# design.net
KiCad netlist of a schematic drawn in Altium Designer
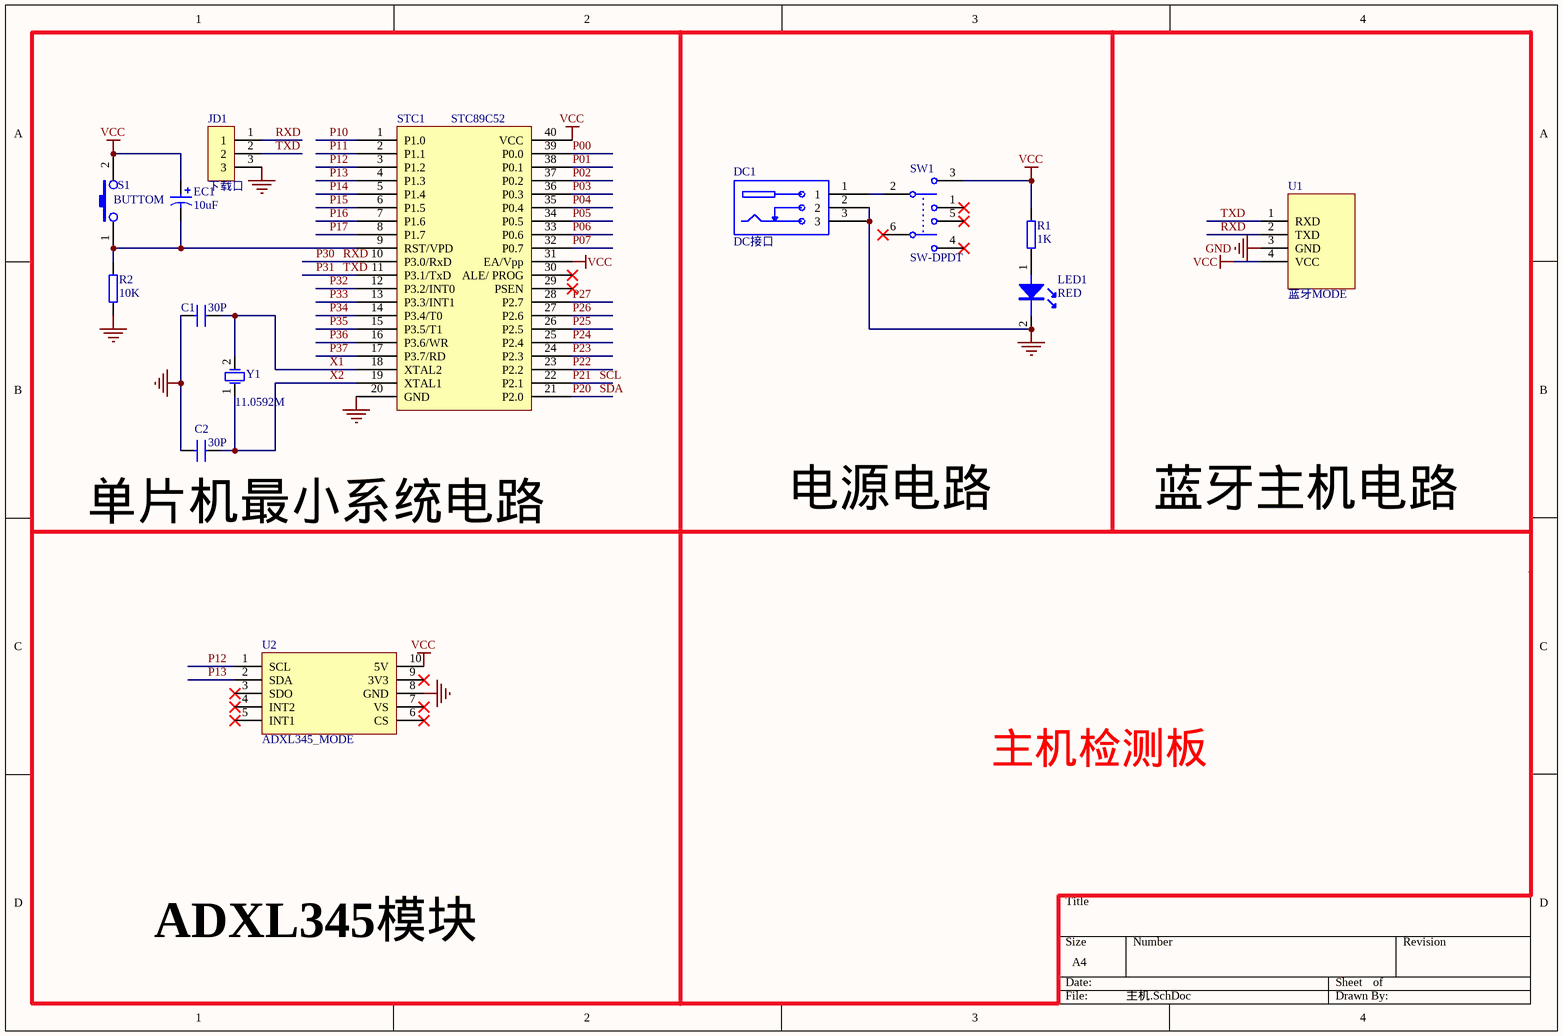
[diagram p0: 主机.SchDoc]

(export (version "E")
  (design (tool "Eeschema 10.0.6"))
  (components
    (comp (ref "C1")
      (value "30P")
      (footprint "RAD-0.1")
      (description "无极性电容")
      (libsource (lib "参考") (part "CAP"))
    )
    (comp (ref "C2")
      (value "30P")
      (footprint "RAD-0.1")
      (description "无极性电容")
      (libsource (lib "参考") (part "CAP"))
    )
    (comp (ref "DC1")
      (value "DC接口")
      (footprint "DC-JACK-002")
      (description "DC接口（分大小）")
      (libsource (lib "参考") (part "DC接口"))
    )
    (comp (ref "EC1")
      (value "10uF")
      (footprint "RB.1/.2")
      (description "极性电容")
      (libsource (lib "参考") (part "CAP_EC"))
    )
    (comp (ref "JD1")
      (value "下载口")
      (footprint "下载串口")
      (description "下载口2.54排针")
      (libsource (lib "参考") (part "下载口"))
    )
    (comp (ref "LED1")
      (value "RED")
      (footprint "LED_D3MM12")
      (description "LED灯")
      (libsource (lib "参考") (part "LED"))
    )
    (comp (ref "R1")
      (value "1K")
      (footprint "AXIAL0.3")
      (description "电阻")
      (libsource (lib "参考") (part "RES"))
    )
    (comp (ref "R2")
      (value "10K")
      (footprint "AXIAL0.3")
      (description "电阻")
      (libsource (lib "参考") (part "RES"))
    )
    (comp (ref "S1")
      (value "BUTTOM")
      (footprint "BUTTOM_6x6DIP")
      (description "按键")
      (libsource (lib "参考") (part "BUTTOM"))
    )
    (comp (ref "STC1")
      (value "STC89C52")
      (footprint "STC89")
      (description "51单片机")
      (libsource (lib "参考") (part "STC51"))
    )
    (comp (ref "SW1")
      (value "SW-DPDT")
      (footprint "SW")
      (description "电源开关")
      (fields (field (name "PUBLISHER") "Altium Limited"))
      (libsource (lib "参考") (part "SW-DPDT"))
    )
    (comp (ref "U1")
      (value "蓝牙MODE")
      (footprint "蓝牙MODE平放")
      (description "蓝牙模块")
      (libsource (lib "参考") (part "蓝牙MODE"))
    )
    (comp (ref "U2")
      (value "ADXL345_MODE")
      (footprint "ADXL345MODE")
      (description "ADXL345 倾斜模块")
      (libsource (lib "参考") (part "ADXL345_MODE"))
    )
    (comp (ref "Y1")
      (value "11.0592M")
      (footprint "X_HC-49")
      (description "晶振")
      (libsource (lib "参考") (part "XTAL DIP"))
    )
  )
  (nets
    (net (code "1") (name "/P00") (class "Default")
      (node (ref "STC1") (pin "39") (pinfunction "P0.0_39") (pintype "passive"))
    )
    (net (code "2") (name "/P01") (class "Default")
      (node (ref "STC1") (pin "38") (pinfunction "P0.1_38") (pintype "passive"))
    )
    (net (code "3") (name "/P02") (class "Default")
      (node (ref "STC1") (pin "37") (pinfunction "P0.2_37") (pintype "passive"))
    )
    (net (code "4") (name "/P03") (class "Default")
      (node (ref "STC1") (pin "36") (pinfunction "P0.3_36") (pintype "passive"))
    )
    (net (code "5") (name "/P04") (class "Default")
      (node (ref "STC1") (pin "35") (pinfunction "P0.4_35") (pintype "passive"))
    )
    (net (code "6") (name "/P05") (class "Default")
      (node (ref "STC1") (pin "34") (pinfunction "P0.5_34") (pintype "passive"))
    )
    (net (code "7") (name "/P06") (class "Default")
      (node (ref "STC1") (pin "33") (pinfunction "P0.6_33") (pintype "passive"))
    )
    (net (code "8") (name "/P07") (class "Default")
      (node (ref "STC1") (pin "32") (pinfunction "P0.7_32") (pintype "passive"))
    )
    (net (code "9") (name "/P10") (class "Default")
      (node (ref "STC1") (pin "1") (pinfunction "P1.0_1") (pintype "passive"))
    )
    (net (code "10") (name "/P11") (class "Default")
      (node (ref "STC1") (pin "2") (pinfunction "P1.1_2") (pintype "passive"))
    )
    (net (code "11") (name "/P12") (class "Default")
      (node (ref "STC1") (pin "3") (pinfunction "P1.2_3") (pintype "passive"))
      (node (ref "U2") (pin "1") (pinfunction "SCL_1") (pintype "passive"))
    )
    (net (code "12") (name "/P13") (class "Default")
      (node (ref "STC1") (pin "4") (pinfunction "P1.3_4") (pintype "passive"))
      (node (ref "U2") (pin "2") (pinfunction "SDA_2") (pintype "passive"))
    )
    (net (code "13") (name "/P14") (class "Default")
      (node (ref "STC1") (pin "5") (pinfunction "P1.4_5") (pintype "passive"))
    )
    (net (code "14") (name "/P15") (class "Default")
      (node (ref "STC1") (pin "6") (pinfunction "P1.5_6") (pintype "passive"))
    )
    (net (code "15") (name "/P16") (class "Default")
      (node (ref "STC1") (pin "7") (pinfunction "P1.6_7") (pintype "passive"))
    )
    (net (code "16") (name "/P17") (class "Default")
      (node (ref "STC1") (pin "8") (pinfunction "P1.7_8") (pintype "passive"))
    )
    (net (code "17") (name "/P20") (class "Default")
      (node (ref "STC1") (pin "21") (pinfunction "P2.0_21") (pintype "passive"))
    )
    (net (code "18") (name "/P21") (class "Default")
      (node (ref "STC1") (pin "22") (pinfunction "P2.1_22") (pintype "passive"))
    )
    (net (code "19") (name "/P22") (class "Default")
      (node (ref "STC1") (pin "23") (pinfunction "P2.2_23") (pintype "passive"))
    )
    (net (code "20") (name "/P23") (class "Default")
      (node (ref "STC1") (pin "24") (pinfunction "P2.3_24") (pintype "passive"))
    )
    (net (code "21") (name "/P24") (class "Default")
      (node (ref "STC1") (pin "25") (pinfunction "P2.4_25") (pintype "passive"))
    )
    (net (code "22") (name "/P25") (class "Default")
      (node (ref "STC1") (pin "26") (pinfunction "P2.5_26") (pintype "passive"))
    )
    (net (code "23") (name "/P26") (class "Default")
      (node (ref "STC1") (pin "27") (pinfunction "P2.6_27") (pintype "passive"))
    )
    (net (code "24") (name "/P27") (class "Default")
      (node (ref "STC1") (pin "28") (pinfunction "P2.7_28") (pintype "passive"))
    )
    (net (code "25") (name "/P30") (class "Default")
      (node (ref "JD1") (pin "1") (pinfunction "1_1") (pintype "passive"))
      (node (ref "STC1") (pin "10") (pinfunction "P3.0/RxD_10") (pintype "passive"))
      (node (ref "U1") (pin "2") (pinfunction "TXD_2") (pintype "passive"))
    )
    (net (code "26") (name "/P31") (class "Default")
      (node (ref "JD1") (pin "2") (pinfunction "2_2") (pintype "passive"))
      (node (ref "STC1") (pin "11") (pinfunction "P3.1/TxD_11") (pintype "passive"))
      (node (ref "U1") (pin "1") (pinfunction "RXD_1") (pintype "passive"))
    )
    (net (code "27") (name "/P32") (class "Default")
      (node (ref "STC1") (pin "12") (pinfunction "P3.2/INT0_12") (pintype "passive"))
    )
    (net (code "28") (name "/P33") (class "Default")
      (node (ref "STC1") (pin "13") (pinfunction "P3.3/INT1_13") (pintype "passive"))
    )
    (net (code "29") (name "/P34") (class "Default")
      (node (ref "STC1") (pin "14") (pinfunction "P3.4/T0_14") (pintype "passive"))
    )
    (net (code "30") (name "/P35") (class "Default")
      (node (ref "STC1") (pin "15") (pinfunction "P3.5/T1_15") (pintype "passive"))
    )
    (net (code "31") (name "/P36") (class "Default")
      (node (ref "STC1") (pin "16") (pinfunction "P3.6/WR_16") (pintype "passive"))
    )
    (net (code "32") (name "/P37") (class "Default")
      (node (ref "STC1") (pin "17") (pinfunction "P3.7/RD_17") (pintype "passive"))
    )
    (net (code "33") (name "/X1") (class "Default")
      (node (ref "C1") (pin "2") (pinfunction "2_2") (pintype "passive"))
      (node (ref "STC1") (pin "18") (pinfunction "XTAL2_18") (pintype "passive"))
      (node (ref "Y1") (pin "2") (pinfunction "OSC2_2") (pintype "passive"))
    )
    (net (code "34") (name "/X2") (class "Default")
      (node (ref "C2") (pin "2") (pinfunction "2_2") (pintype "passive"))
      (node (ref "STC1") (pin "19") (pinfunction "XTAL1_19") (pintype "passive"))
      (node (ref "Y1") (pin "1") (pinfunction "OSC1_1") (pintype "passive"))
    )
    (net (code "35") (name "GND") (class "Default")
      (node (ref "C1") (pin "1") (pinfunction "1_1") (pintype "passive"))
      (node (ref "C2") (pin "1") (pinfunction "1_1") (pintype "passive"))
      (node (ref "DC1") (pin "2") (pinfunction "2_2") (pintype "passive"))
      (node (ref "DC1") (pin "3") (pinfunction "3_3") (pintype "passive"))
      (node (ref "JD1") (pin "3") (pinfunction "3_3") (pintype "passive"))
      (node (ref "LED1") (pin "2") (pinfunction "2_2") (pintype "passive"))
      (node (ref "R2") (pin "1") (pinfunction "1_1") (pintype "passive"))
      (node (ref "STC1") (pin "20") (pinfunction "GND_20") (pintype "passive"))
      (node (ref "U1") (pin "3") (pinfunction "GND_3") (pintype "passive"))
      (node (ref "U2") (pin "8") (pinfunction "GND_8") (pintype "passive"))
    )
    (net (code "36") (name "Net-(DC1-Pad1)") (class "Default")
      (node (ref "DC1") (pin "1") (pinfunction "1_1") (pintype "passive"))
      (node (ref "SW1") (pin "2") (pinfunction "2_2") (pintype "passive"))
    )
    (net (code "37") (name "Net-(LED1-Pad1)") (class "Default")
      (node (ref "LED1") (pin "1") (pinfunction "1_1") (pintype "passive"))
      (node (ref "R1") (pin "1") (pinfunction "1_1") (pintype "passive"))
    )
    (net (code "38") (name "Net-(STC1-RST{slash}VPD)") (class "Default")
      (node (ref "EC1") (pin "2") (pinfunction "2_2") (pintype "passive"))
      (node (ref "R2") (pin "2") (pinfunction "2_2") (pintype "passive"))
      (node (ref "S1") (pin "1") (pinfunction "1_1") (pintype "passive"))
      (node (ref "STC1") (pin "9") (pinfunction "RST/VPD_9") (pintype "passive"))
    )
    (net (code "39") (name "VCC") (class "Default")
      (node (ref "EC1") (pin "1") (pinfunction "1_1") (pintype "passive"))
      (node (ref "R1") (pin "2") (pinfunction "2_2") (pintype "passive"))
      (node (ref "S1") (pin "2") (pinfunction "2_2") (pintype "passive"))
      (node (ref "STC1") (pin "31") (pinfunction "EA/Vpp_31") (pintype "passive"))
      (node (ref "STC1") (pin "40") (pinfunction "VCC_40") (pintype "passive"))
      (node (ref "SW1") (pin "3") (pinfunction "3_3") (pintype "passive"))
      (node (ref "U1") (pin "4") (pinfunction "VCC_4") (pintype "passive"))
      (node (ref "U2") (pin "10") (pinfunction "5V_10") (pintype "passive"))
    )
    (net (code "40") (name "unconnected-(STC1-ALE{slash}_PROG-Pad30)") (class "Default")
      (node (ref "STC1") (pin "30") (pinfunction "ALE/_PROG_30") (pintype "passive+no_connect"))
    )
    (net (code "41") (name "unconnected-(STC1-PSEN-Pad29)") (class "Default")
      (node (ref "STC1") (pin "29") (pinfunction "PSEN_29") (pintype "passive+no_connect"))
    )
    (net (code "42") (name "unconnected-(SW1-Pad1)") (class "Default")
      (node (ref "SW1") (pin "1") (pinfunction "1_1") (pintype "passive+no_connect"))
    )
    (net (code "43") (name "unconnected-(SW1-Pad4)") (class "Default")
      (node (ref "SW1") (pin "4") (pinfunction "4_4") (pintype "passive+no_connect"))
    )
    (net (code "44") (name "unconnected-(SW1-Pad5)") (class "Default")
      (node (ref "SW1") (pin "5") (pinfunction "5_5") (pintype "passive+no_connect"))
    )
    (net (code "45") (name "unconnected-(SW1-Pad6)") (class "Default")
      (node (ref "SW1") (pin "6") (pinfunction "6_6") (pintype "passive+no_connect"))
    )
    (net (code "46") (name "unconnected-(U2-3V3-Pad9)") (class "Default")
      (node (ref "U2") (pin "9") (pinfunction "3V3_9") (pintype "passive+no_connect"))
    )
    (net (code "47") (name "unconnected-(U2-CS-Pad6)") (class "Default")
      (node (ref "U2") (pin "6") (pinfunction "CS_6") (pintype "passive+no_connect"))
    )
    (net (code "48") (name "unconnected-(U2-INT1-Pad5)") (class "Default")
      (node (ref "U2") (pin "5") (pinfunction "INT1_5") (pintype "passive+no_connect"))
    )
    (net (code "49") (name "unconnected-(U2-INT2-Pad4)") (class "Default")
      (node (ref "U2") (pin "4") (pinfunction "INT2_4") (pintype "passive+no_connect"))
    )
    (net (code "50") (name "unconnected-(U2-SDO-Pad3)") (class "Default")
      (node (ref "U2") (pin "3") (pinfunction "SDO_3") (pintype "passive+no_connect"))
    )
    (net (code "51") (name "unconnected-(U2-VS-Pad7)") (class "Default")
      (node (ref "U2") (pin "7") (pinfunction "VS_7") (pintype "passive+no_connect"))
    )
  )
)
